# Motions.net
KiCad netlist of a schematic drawn in Altium Designer
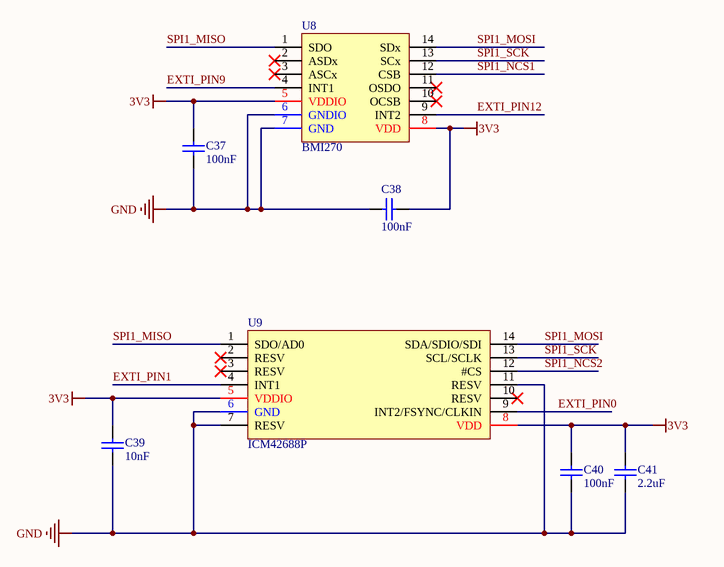
[diagram p0: Motions.SchDoc]

(export (version "E")
  (design (tool "Eeschema 10.0.6"))
  (components
    (comp (ref "C37")
      (value "100nF")
      (footprint "C0402_NS")
      (description "Capacitance 0402")
      (libsource (lib "AxisQuad Components Lib") (part "C0402"))
    )
    (comp (ref "C38")
      (value "100nF")
      (footprint "C0402_NS")
      (description "Capacitance 0402")
      (libsource (lib "AxisQuad Components Lib") (part "C0402"))
    )
    (comp (ref "C39")
      (value "10nF")
      (footprint "C0402_NS")
      (description "Capacitance 0402")
      (libsource (lib "AxisQuad Components Lib") (part "C0402"))
    )
    (comp (ref "C40")
      (value "100nF")
      (footprint "C0402_NS")
      (description "Capacitance 0402")
      (libsource (lib "AxisQuad Components Lib") (part "C0402"))
    )
    (comp (ref "C41")
      (value "2.2uF")
      (footprint "C0402_NS")
      (description "Capacitance 0402")
      (libsource (lib "AxisQuad Components Lib") (part "C0402"))
    )
    (comp (ref "U8")
      (value "BMI270")
      (footprint "LGA-14")
      (description "6-axis, smart, low power Inertial Measurement Unit for high-performance applications")
      (libsource (lib "AxisQuad Components Lib") (part "BMI270"))
    )
    (comp (ref "U9")
      (value "ICM42688P")
      (footprint "LGA-14")
      (description "TDK Invensense high-performance 6-DOF Motion Tracking MEMS")
      (libsource (lib "DBS Components Lib") (part "ICM42688P"))
    )
  )
  (nets
    (net (code "1") (name "/EXTI_PIN0") (class "Default")
      (node (ref "U9") (pin "9") (pinfunction "INT2/FSYNC/CLKIN_9") (pintype "passive"))
    )
    (net (code "2") (name "/EXTI_PIN1") (class "Default")
      (node (ref "U9") (pin "4") (pinfunction "INT1_4") (pintype "passive"))
    )
    (net (code "3") (name "/EXTI_PIN9") (class "Default")
      (node (ref "U8") (pin "4") (pinfunction "INT1_4") (pintype "passive"))
    )
    (net (code "4") (name "/EXTI_PIN12") (class "Default")
      (node (ref "U8") (pin "9") (pinfunction "INT2_9") (pintype "passive"))
    )
    (net (code "5") (name "/SPI1_MISO") (class "Default")
      (node (ref "U8") (pin "1") (pinfunction "SDO_1") (pintype "passive"))
      (node (ref "U9") (pin "1") (pinfunction "SDO/AD0_1") (pintype "passive"))
    )
    (net (code "6") (name "/SPI1_MOSI") (class "Default")
      (node (ref "U8") (pin "14") (pinfunction "SDx_14") (pintype "passive"))
      (node (ref "U9") (pin "14") (pinfunction "SDA/SDIO/SDI_14") (pintype "passive"))
    )
    (net (code "7") (name "/SPI1_NCS1") (class "Default")
      (node (ref "U8") (pin "12") (pinfunction "CSB_12") (pintype "passive"))
    )
    (net (code "8") (name "/SPI1_NCS2") (class "Default")
      (node (ref "U9") (pin "12") (pinfunction "#CS_12") (pintype "passive"))
    )
    (net (code "9") (name "/SPI1_SCK") (class "Default")
      (node (ref "U8") (pin "13") (pinfunction "SCx_13") (pintype "passive"))
      (node (ref "U9") (pin "13") (pinfunction "SCL/SCLK_13") (pintype "passive"))
    )
    (net (code "10") (name "3V3") (class "Default")
      (node (ref "C37") (pin "2") (pinfunction "2_2") (pintype "passive"))
      (node (ref "C38") (pin "2") (pinfunction "2_2") (pintype "passive"))
      (node (ref "C39") (pin "2") (pinfunction "2_2") (pintype "passive"))
      (node (ref "C40") (pin "2") (pinfunction "2_2") (pintype "passive"))
      (node (ref "C41") (pin "2") (pinfunction "2_2") (pintype "passive"))
      (node (ref "U8") (pin "5") (pinfunction "VDDIO_5") (pintype "passive"))
      (node (ref "U8") (pin "8") (pinfunction "VDD_8") (pintype "passive"))
      (node (ref "U9") (pin "5") (pinfunction "VDDIO_5") (pintype "passive"))
      (node (ref "U9") (pin "8") (pinfunction "VDD_8") (pintype "passive"))
    )
    (net (code "11") (name "GND") (class "Default")
      (node (ref "C37") (pin "1") (pinfunction "1_1") (pintype "passive"))
      (node (ref "C38") (pin "1") (pinfunction "1_1") (pintype "passive"))
      (node (ref "C39") (pin "1") (pinfunction "1_1") (pintype "passive"))
      (node (ref "C40") (pin "1") (pinfunction "1_1") (pintype "passive"))
      (node (ref "C41") (pin "1") (pinfunction "1_1") (pintype "passive"))
      (node (ref "U8") (pin "6") (pinfunction "GNDIO_6") (pintype "passive"))
      (node (ref "U8") (pin "7") (pinfunction "GND_7") (pintype "passive"))
      (node (ref "U9") (pin "11") (pinfunction "RESV_11") (pintype "passive"))
      (node (ref "U9") (pin "6") (pinfunction "GND_6") (pintype "passive"))
      (node (ref "U9") (pin "7") (pinfunction "RESV_7") (pintype "passive"))
    )
    (net (code "12") (name "unconnected-(U8-ASCx-Pad3)") (class "Default")
      (node (ref "U8") (pin "3") (pinfunction "ASCx_3") (pintype "passive+no_connect"))
    )
    (net (code "13") (name "unconnected-(U8-ASDx-Pad2)") (class "Default")
      (node (ref "U8") (pin "2") (pinfunction "ASDx_2") (pintype "passive+no_connect"))
    )
    (net (code "14") (name "unconnected-(U8-OCSB-Pad10)") (class "Default")
      (node (ref "U8") (pin "10") (pinfunction "OCSB_10") (pintype "passive+no_connect"))
    )
    (net (code "15") (name "unconnected-(U8-OSDO-Pad11)") (class "Default")
      (node (ref "U8") (pin "11") (pinfunction "OSDO_11") (pintype "passive+no_connect"))
    )
    (net (code "16") (name "unconnected-(U9-RESV-Pad2)") (class "Default")
      (node (ref "U9") (pin "2") (pinfunction "RESV_2") (pintype "passive+no_connect"))
    )
    (net (code "17") (name "unconnected-(U9-RESV-Pad3)") (class "Default")
      (node (ref "U9") (pin "3") (pinfunction "RESV_3") (pintype "passive+no_connect"))
    )
    (net (code "18") (name "unconnected-(U9-RESV-Pad10)") (class "Default")
      (node (ref "U9") (pin "10") (pinfunction "RESV_10") (pintype "passive+no_connect"))
    )
  )
)
